# hole_field.net
KiCad netlist of a schematic drawn in Altium Designer
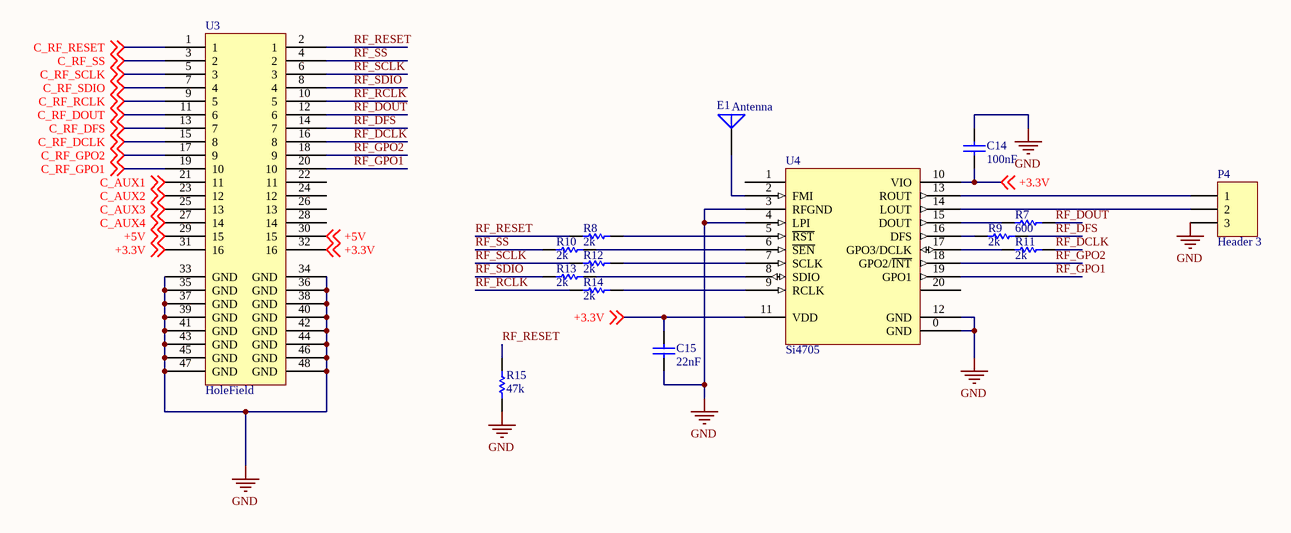
[diagram p0: hole_field.SchDoc]

(export (version "E")
  (design (tool "Eeschema 10.0.6"))
  (components
    (comp (ref "C14")
      (value "100nF")
      (footprint "CHIP0805")
      (description "Capacitor")
      (fields (field (name "PUBLISHER") "Altium Limited"))
      (libsource (lib "Miscellaneous Devices") (part "Cap"))
    )
    (comp (ref "C15")
      (value "22nF")
      (footprint "CHIP0805")
      (description "Capacitor")
      (fields (field (name "PUBLISHER") "Altium Limited"))
      (libsource (lib "Miscellaneous Devices") (part "Cap"))
    )
    (comp (ref "E1")
      (value "Antenna")
      (footprint "PIN1")
      (description "Generic Antenna")
      (fields (field (name "PUBLISHER") "Altium Limited"))
      (libsource (lib "Miscellaneous Devices") (part "Antenna"))
    )
    (comp (ref "P4")
      (value "Header 3")
      (footprint "HDR1X3")
      (description "Header, 3-Pin")
      (fields (field (name "PUBLISHER") "Altium Limited"))
      (libsource (lib "Miscellaneous Connectors") (part "Header 3"))
    )
    (comp (ref "R7")
      (value "600")
      (footprint "CHIP0805")
      (description "Resistor")
      (fields (field (name "PUBLISHER") "Altium Limited"))
      (libsource (lib "Miscellaneous Devices") (part "Res1"))
    )
    (comp (ref "R8")
      (value "2k")
      (footprint "CHIP0805")
      (description "Resistor")
      (fields (field (name "PUBLISHER") "Altium Limited"))
      (libsource (lib "Miscellaneous Devices") (part "Res1"))
    )
    (comp (ref "R9")
      (value "2k")
      (footprint "CHIP0805")
      (description "Resistor")
      (fields (field (name "PUBLISHER") "Altium Limited"))
      (libsource (lib "Miscellaneous Devices") (part "Res1"))
    )
    (comp (ref "R10")
      (value "2k")
      (footprint "CHIP0805")
      (description "Resistor")
      (fields (field (name "PUBLISHER") "Altium Limited"))
      (libsource (lib "Miscellaneous Devices") (part "Res1"))
    )
    (comp (ref "R11")
      (value "2k")
      (footprint "CHIP0805")
      (description "Resistor")
      (fields (field (name "PUBLISHER") "Altium Limited"))
      (libsource (lib "Miscellaneous Devices") (part "Res1"))
    )
    (comp (ref "R12")
      (value "2k")
      (footprint "CHIP0805")
      (description "Resistor")
      (fields (field (name "PUBLISHER") "Altium Limited"))
      (libsource (lib "Miscellaneous Devices") (part "Res1"))
    )
    (comp (ref "R13")
      (value "2k")
      (footprint "CHIP0805")
      (description "Resistor")
      (fields (field (name "PUBLISHER") "Altium Limited"))
      (libsource (lib "Miscellaneous Devices") (part "Res1"))
    )
    (comp (ref "R14")
      (value "2k")
      (footprint "CHIP0805")
      (description "Resistor")
      (fields (field (name "PUBLISHER") "Altium Limited"))
      (libsource (lib "Miscellaneous Devices") (part "Res1"))
    )
    (comp (ref "R15")
      (value "47k")
      (footprint "CHIP0805")
      (description "Resistor")
      (fields (field (name "PUBLISHER") "Altium Limited"))
      (libsource (lib "Miscellaneous Devices") (part "Res1"))
    )
    (comp (ref "U3")
      (value "HoleField")
      (footprint "HoleField")
      (libsource (lib "Auxiliary") (part "HoleField"))
    )
    (comp (ref "U4")
      (value "Si4705")
      (footprint "QFN50P300X300X60-20N")
      (libsource (lib "mil01") (part "Si4705"))
    )
  )
  (nets
    (net (code "1") (name "+3.3V") (class "Default")
      (node (ref "C14") (pin "1") (pinfunction "1_1") (pintype "passive"))
      (node (ref "C15") (pin "2") (pinfunction "2_2") (pintype "passive"))
      (node (ref "U3") (pin "31") (pinfunction "16_31") (pintype "passive"))
      (node (ref "U3") (pin "32") (pinfunction "16_32") (pintype "passive"))
      (node (ref "U4") (pin "10") (pinfunction "VIO_10") (pintype "power_in"))
      (node (ref "U4") (pin "11") (pinfunction "VDD_11") (pintype "power_in"))
    )
    (net (code "2") (name "+5V") (class "Default")
      (node (ref "U3") (pin "29") (pinfunction "15_29") (pintype "passive"))
      (node (ref "U3") (pin "30") (pinfunction "15_30") (pintype "passive"))
    )
    (net (code "3") (name "/RF_DCLK") (class "Default")
      (node (ref "R11") (pin "2") (pinfunction "2_2") (pintype "passive"))
      (node (ref "U3") (pin "16") (pinfunction "8_16") (pintype "passive"))
    )
    (net (code "4") (name "/RF_DFS") (class "Default")
      (node (ref "R9") (pin "2") (pinfunction "2_2") (pintype "passive"))
      (node (ref "U3") (pin "14") (pinfunction "7_14") (pintype "passive"))
    )
    (net (code "5") (name "/RF_DOUT") (class "Default")
      (node (ref "R7") (pin "2") (pinfunction "2_2") (pintype "passive"))
      (node (ref "U3") (pin "12") (pinfunction "6_12") (pintype "passive"))
    )
    (net (code "6") (name "/RF_GPO1") (class "Default")
      (node (ref "U3") (pin "20") (pinfunction "10_20") (pintype "passive"))
      (node (ref "U4") (pin "19") (pinfunction "GPO1_19") (pintype "output"))
    )
    (net (code "7") (name "/RF_GPO2") (class "Default")
      (node (ref "U3") (pin "18") (pinfunction "9_18") (pintype "passive"))
      (node (ref "U4") (pin "18") (pinfunction "GPO2/~{INT}_18") (pintype "output"))
    )
    (net (code "8") (name "/RF_RCLK") (class "Default")
      (node (ref "R14") (pin "1") (pinfunction "1_1") (pintype "passive"))
      (node (ref "U3") (pin "10") (pinfunction "5_10") (pintype "passive"))
    )
    (net (code "9") (name "/RF_RESET") (class "Default")
      (node (ref "R15") (pin "2") (pinfunction "2_2") (pintype "passive"))
      (node (ref "R8") (pin "1") (pinfunction "1_1") (pintype "passive"))
      (node (ref "U3") (pin "2") (pinfunction "1_2") (pintype "passive"))
    )
    (net (code "10") (name "/RF_SCLK") (class "Default")
      (node (ref "R12") (pin "1") (pinfunction "1_1") (pintype "passive"))
      (node (ref "U3") (pin "6") (pinfunction "3_6") (pintype "passive"))
    )
    (net (code "11") (name "/RF_SDIO") (class "Default")
      (node (ref "R13") (pin "1") (pinfunction "1_1") (pintype "passive"))
      (node (ref "U3") (pin "8") (pinfunction "4_8") (pintype "passive"))
    )
    (net (code "12") (name "/RF_~{SS}") (class "Default")
      (node (ref "R10") (pin "1") (pinfunction "1_1") (pintype "passive"))
      (node (ref "U3") (pin "4") (pinfunction "2_4") (pintype "passive"))
    )
    (net (code "13") (name "C_AUX1") (class "Default")
      (node (ref "U3") (pin "21") (pinfunction "11_21") (pintype "passive"))
    )
    (net (code "14") (name "C_AUX2") (class "Default")
      (node (ref "U3") (pin "23") (pinfunction "12_23") (pintype "passive"))
    )
    (net (code "15") (name "C_AUX3") (class "Default")
      (node (ref "U3") (pin "25") (pinfunction "13_25") (pintype "passive"))
    )
    (net (code "16") (name "C_AUX4") (class "Default")
      (node (ref "U3") (pin "27") (pinfunction "14_27") (pintype "passive"))
    )
    (net (code "17") (name "C_RF_DCLK") (class "Default")
      (node (ref "U3") (pin "15") (pinfunction "8_15") (pintype "passive"))
    )
    (net (code "18") (name "C_RF_DFS") (class "Default")
      (node (ref "U3") (pin "13") (pinfunction "7_13") (pintype "passive"))
    )
    (net (code "19") (name "C_RF_DOUT") (class "Default")
      (node (ref "U3") (pin "11") (pinfunction "6_11") (pintype "passive"))
    )
    (net (code "20") (name "C_RF_GPO1") (class "Default")
      (node (ref "U3") (pin "19") (pinfunction "10_19") (pintype "passive"))
    )
    (net (code "21") (name "C_RF_GPO2") (class "Default")
      (node (ref "U3") (pin "17") (pinfunction "9_17") (pintype "passive"))
    )
    (net (code "22") (name "C_RF_RCLK") (class "Default")
      (node (ref "U3") (pin "9") (pinfunction "5_9") (pintype "passive"))
    )
    (net (code "23") (name "C_RF_RESET") (class "Default")
      (node (ref "U3") (pin "1") (pinfunction "1_1") (pintype "passive"))
    )
    (net (code "24") (name "C_RF_SCLK") (class "Default")
      (node (ref "U3") (pin "5") (pinfunction "3_5") (pintype "passive"))
    )
    (net (code "25") (name "C_RF_SDIO") (class "Default")
      (node (ref "U3") (pin "7") (pinfunction "4_7") (pintype "passive"))
    )
    (net (code "26") (name "C_RF_SS") (class "Default")
      (node (ref "U3") (pin "3") (pinfunction "2_3") (pintype "passive"))
    )
    (net (code "27") (name "GND") (class "Default")
      (node (ref "C14") (pin "2") (pinfunction "2_2") (pintype "passive"))
      (node (ref "C15") (pin "1") (pinfunction "1_1") (pintype "passive"))
      (node (ref "P4") (pin "3") (pinfunction "3_3") (pintype "passive"))
      (node (ref "R15") (pin "1") (pinfunction "1_1") (pintype "passive"))
      (node (ref "U3") (pin "33") (pinfunction "GND_33") (pintype "passive"))
      (node (ref "U3") (pin "34") (pinfunction "GND_34") (pintype "passive"))
      (node (ref "U3") (pin "35") (pinfunction "GND_35") (pintype "passive"))
      (node (ref "U3") (pin "36") (pinfunction "GND_36") (pintype "passive"))
      (node (ref "U3") (pin "37") (pinfunction "GND_37") (pintype "passive"))
      (node (ref "U3") (pin "38") (pinfunction "GND_38") (pintype "passive"))
      (node (ref "U3") (pin "39") (pinfunction "GND_39") (pintype "passive"))
      (node (ref "U3") (pin "40") (pinfunction "GND_40") (pintype "passive"))
      (node (ref "U3") (pin "41") (pinfunction "GND_41") (pintype "passive"))
      (node (ref "U3") (pin "42") (pinfunction "GND_42") (pintype "passive"))
      (node (ref "U3") (pin "43") (pinfunction "GND_43") (pintype "passive"))
      (node (ref "U3") (pin "44") (pinfunction "GND_44") (pintype "passive"))
      (node (ref "U3") (pin "45") (pinfunction "GND_45") (pintype "passive"))
      (node (ref "U3") (pin "46") (pinfunction "GND_46") (pintype "passive"))
      (node (ref "U3") (pin "47") (pinfunction "GND_47") (pintype "passive"))
      (node (ref "U3") (pin "48") (pinfunction "GND_48") (pintype "passive"))
      (node (ref "U4") (pin "0") (pinfunction "GND_0") (pintype "power_in"))
      (node (ref "U4") (pin "12") (pinfunction "GND_12") (pintype "power_in"))
      (node (ref "U4") (pin "3") (pinfunction "RFGND_3") (pintype "power_in"))
      (node (ref "U4") (pin "4") (pinfunction "LPI_4") (pintype "input"))
    )
    (net (code "28") (name "Net-(E1-A)") (class "Default")
      (node (ref "E1") (pin "1") (pinfunction "A_1") (pintype "passive"))
      (node (ref "U4") (pin "2") (pinfunction "FMI_2") (pintype "input"))
    )
    (net (code "29") (name "Net-(U4-DFS)") (class "Default")
      (node (ref "R9") (pin "1") (pinfunction "1_1") (pintype "passive"))
      (node (ref "U4") (pin "16") (pinfunction "DFS_16") (pintype "output"))
    )
    (net (code "30") (name "Net-(U4-DOUT)") (class "Default")
      (node (ref "R7") (pin "1") (pinfunction "1_1") (pintype "passive"))
      (node (ref "U4") (pin "15") (pinfunction "DOUT_15") (pintype "output"))
    )
    (net (code "31") (name "Net-(U4-GPO3{slash}DCLK)") (class "Default")
      (node (ref "R11") (pin "1") (pinfunction "1_1") (pintype "passive"))
      (node (ref "U4") (pin "17") (pinfunction "GPO3/DCLK_17") (pintype "bidirectional"))
    )
    (net (code "32") (name "Net-(U4-LOUT)") (class "Default")
      (node (ref "P4") (pin "2") (pinfunction "2_2") (pintype "passive"))
      (node (ref "U4") (pin "14") (pinfunction "LOUT_14") (pintype "output"))
    )
    (net (code "33") (name "Net-(U4-RCLK)") (class "Default")
      (node (ref "R14") (pin "2") (pinfunction "2_2") (pintype "passive"))
      (node (ref "U4") (pin "9") (pinfunction "RCLK_9") (pintype "input"))
    )
    (net (code "34") (name "Net-(U4-ROUT)") (class "Default")
      (node (ref "P4") (pin "1") (pinfunction "1_1") (pintype "passive"))
      (node (ref "U4") (pin "13") (pinfunction "ROUT_13") (pintype "output"))
    )
    (net (code "35") (name "Net-(U4-SCLK)") (class "Default")
      (node (ref "R12") (pin "2") (pinfunction "2_2") (pintype "passive"))
      (node (ref "U4") (pin "7") (pinfunction "SCLK_7") (pintype "input"))
    )
    (net (code "36") (name "Net-(U4-SDIO)") (class "Default")
      (node (ref "R13") (pin "2") (pinfunction "2_2") (pintype "passive"))
      (node (ref "U4") (pin "8") (pinfunction "SDIO_8") (pintype "bidirectional"))
    )
    (net (code "37") (name "Net-(U4-~{RST})") (class "Default")
      (node (ref "R8") (pin "2") (pinfunction "2_2") (pintype "passive"))
      (node (ref "U4") (pin "5") (pinfunction "~{RST}_5") (pintype "input"))
    )
    (net (code "38") (name "Net-(U4-~{SEN})") (class "Default")
      (node (ref "R10") (pin "2") (pinfunction "2_2") (pintype "passive"))
      (node (ref "U4") (pin "6") (pinfunction "~{SEN}_6") (pintype "input"))
    )
    (net (code "39") (name "unconnected-(U3-11-Pad22)") (class "Default")
      (node (ref "U3") (pin "22") (pinfunction "11_22") (pintype "passive"))
    )
    (net (code "40") (name "unconnected-(U3-12-Pad24)") (class "Default")
      (node (ref "U3") (pin "24") (pinfunction "12_24") (pintype "passive"))
    )
    (net (code "41") (name "unconnected-(U3-13-Pad26)") (class "Default")
      (node (ref "U3") (pin "26") (pinfunction "13_26") (pintype "passive"))
    )
    (net (code "42") (name "unconnected-(U3-14-Pad28)") (class "Default")
      (node (ref "U3") (pin "28") (pinfunction "14_28") (pintype "passive"))
    )
    (net (code "43") (name "unconnected-(U4-NC-Pad1)") (class "Default")
      (node (ref "U4") (pin "1") (pinfunction "NC_1") (pintype "passive"))
    )
    (net (code "44") (name "unconnected-(U4-NC-Pad20)") (class "Default")
      (node (ref "U4") (pin "20") (pinfunction "NC_20") (pintype "passive"))
    )
  )
)
